# Francesco.net
KiCad netlist of a schematic drawn in EAGLE
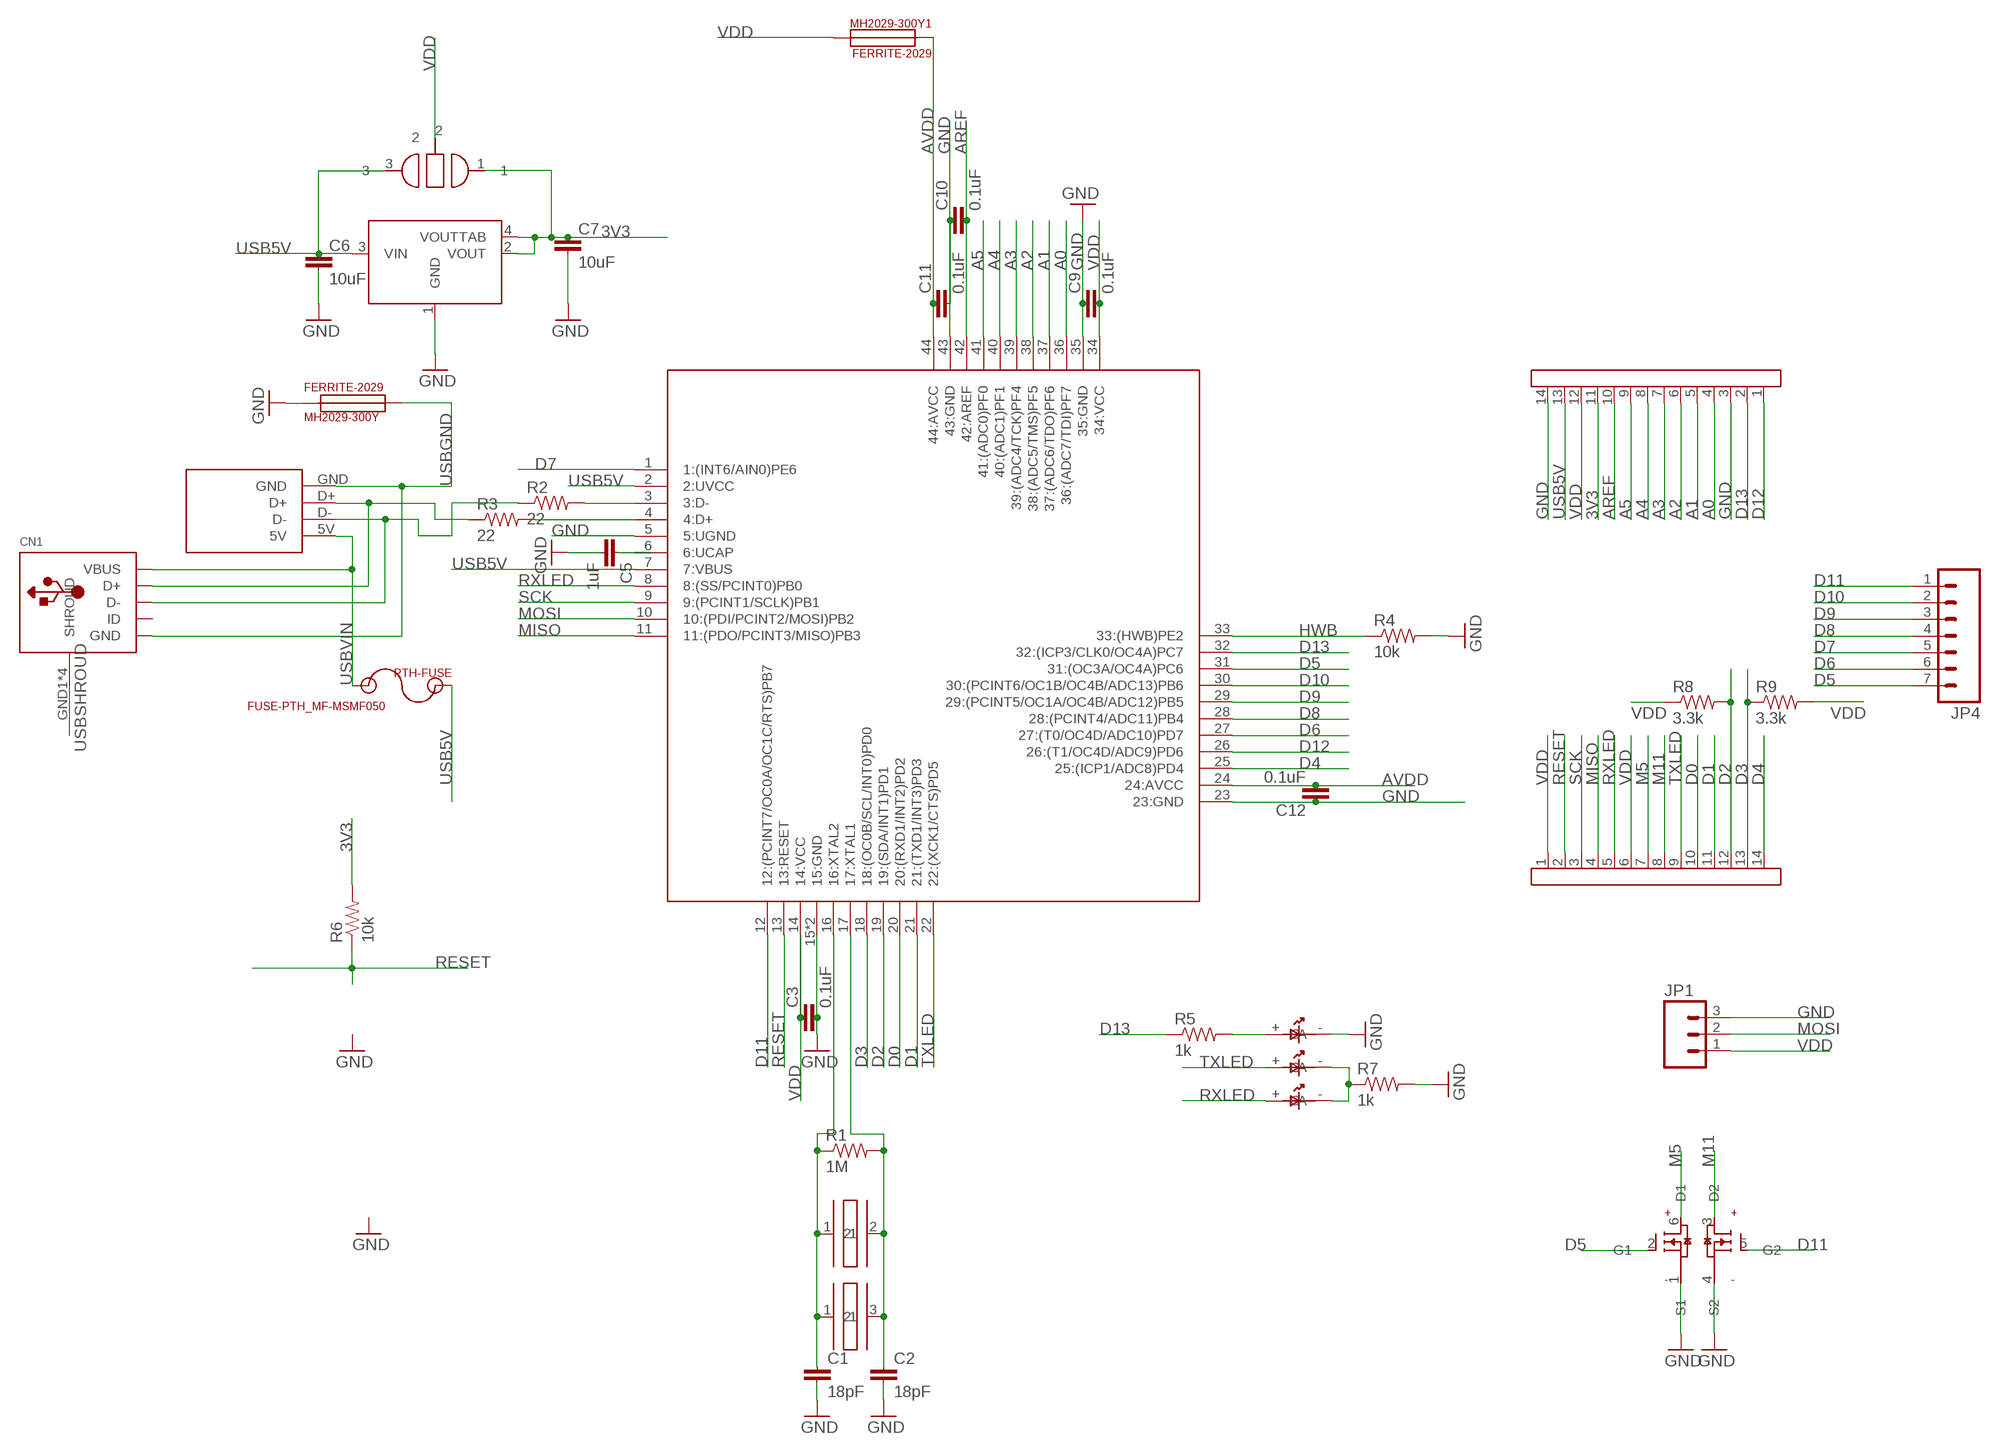
[diagram p0: schematic, sheet 1]

(export (version "E")
  (design (tool "Eeschema 10.0.6"))
  (components
    (comp (ref "C1")
      (value "18pF")
      (footprint "eagle-import:0603-CAP")
      (libsource (lib "eagle-import") (part "CAP0603-CAP"))
    )
    (comp (ref "C2")
      (value "18pF")
      (footprint "eagle-import:0603-CAP")
      (libsource (lib "eagle-import") (part "CAP0603-CAP"))
    )
    (comp (ref "C3")
      (value "0.1uF")
      (footprint "eagle-import:0805")
      (libsource (lib "eagle-import") (part "CAP0805"))
    )
    (comp (ref "C5")
      (value "1uF")
      (footprint "eagle-import:0805")
      (libsource (lib "eagle-import") (part "CAP0805"))
    )
    (comp (ref "C6")
      (value "10uF")
      (footprint "eagle-import:1210")
      (libsource (lib "eagle-import") (part "CAP1210"))
    )
    (comp (ref "C7")
      (value "10uF")
      (footprint "eagle-import:1210")
      (libsource (lib "eagle-import") (part "CAP1210"))
    )
    (comp (ref "C9")
      (value "0.1uF")
      (footprint "eagle-import:0805")
      (libsource (lib "eagle-import") (part "CAP0805"))
    )
    (comp (ref "C10")
      (value "0.1uF")
      (footprint "eagle-import:0805")
      (libsource (lib "eagle-import") (part "CAP0805"))
    )
    (comp (ref "C11")
      (value "0.1uF")
      (footprint "eagle-import:0805")
      (libsource (lib "eagle-import") (part "CAP0805"))
    )
    (comp (ref "C12")
      (value "0.1uF")
      (footprint "eagle-import:0805")
      (libsource (lib "eagle-import") (part "CAP0805"))
    )
    (comp (ref "CN1")
      (value "USBMINIB")
      (footprint "eagle-import:USB-MINIB")
      (libsource (lib "eagle-import") (part "USBMINIB"))
    )
    (comp (ref "JP1")
      (value "M03LOCK")
      (footprint "eagle-import:1X03_LOCK")
      (libsource (lib "eagle-import") (part "M03LOCK"))
    )
    (comp (ref "JP4")
      (value "M07LOCK")
      (footprint "eagle-import:1X07_LOCK")
      (libsource (lib "eagle-import") (part "M07LOCK"))
    )
    (comp (ref "MH2029-300Y")
      (value "FERRITE-2029")
      (footprint "eagle-import:2029")
      (libsource (lib "eagle-import") (part "FERRITE-2029"))
    )
    (comp (ref "MH2029-300Y1")
      (value "FERRITE-2029")
      (footprint "eagle-import:2029")
      (libsource (lib "eagle-import") (part "FERRITE-2029"))
    )
    (comp (ref "PTH-FUSE")
      (value "FUSE-PTH_MF-MSMF050")
      (footprint "eagle-import:MF-MSMF")
      (libsource (lib "eagle-import") (part "FUSE-PTH_MF-MSMF"))
    )
    (comp (ref "R1")
      (value "1M")
      (footprint "eagle-import:0805")
      (libsource (lib "eagle-import") (part "RESISTOR"))
    )
    (comp (ref "R2")
      (value "22")
      (footprint "eagle-import:0603-RES")
      (libsource (lib "eagle-import") (part "RESISTOR0603-RES"))
    )
    (comp (ref "R3")
      (value "22")
      (footprint "eagle-import:0603-RES")
      (libsource (lib "eagle-import") (part "RESISTOR0603-RES"))
    )
    (comp (ref "R4")
      (value "10k")
      (footprint "eagle-import:0805")
      (libsource (lib "eagle-import") (part "RESISTOR"))
    )
    (comp (ref "R5")
      (value "1k")
      (footprint "eagle-import:0805")
      (libsource (lib "eagle-import") (part "RESISTOR"))
    )
    (comp (ref "R6")
      (value "10k")
      (footprint "eagle-import:0805")
      (libsource (lib "eagle-import") (part "RESISTOR"))
    )
    (comp (ref "R7")
      (value "1k")
      (footprint "eagle-import:0805")
      (libsource (lib "eagle-import") (part "RESISTOR"))
    )
    (comp (ref "R8")
      (value "3.3k")
      (footprint "eagle-import:0805")
      (libsource (lib "eagle-import") (part "RESISTOR"))
    )
    (comp (ref "R9")
      (value "3.3k")
      (footprint "eagle-import:0805")
      (libsource (lib "eagle-import") (part "RESISTOR"))
    )
    (comp (ref "U$1")
      (value "ATMEGA32U4")
      (footprint "eagle-import:QFN-44")
      (libsource (lib "eagle-import") (part "ATMEGA32U4"))
    )
    (comp (ref "U$2")
      (value "HC49US")
      (footprint "eagle-import:HC49US")
      (libsource (lib "eagle-import") (part "HC49US"))
    )
    (comp (ref "U$3")
      (value "USB-PCB")
      (footprint "eagle-import:USB_PCB")
      (libsource (lib "eagle-import") (part "USB-PCB"))
    )
    (comp (ref "U$4")
      (value "5V-LDO-ZLDO1117")
      (footprint "eagle-import:ZLDO1117")
      (libsource (lib "eagle-import") (part "5V-LDO-ZLDO1117"))
    )
    (comp (ref "U$5")
      (value "M14")
      (footprint "eagle-import:1X14_LOCK")
      (libsource (lib "eagle-import") (part "M14"))
    )
    (comp (ref "U$6")
      (value "M14")
      (footprint "eagle-import:1X14_LOCK")
      (libsource (lib "eagle-import") (part "M14"))
    )
    (comp (ref "U$7")
      (value "BRIDGE-3")
      (footprint "eagle-import:BRIDGE-3")
      (libsource (lib "eagle-import") (part "BRIDGE-3"))
    )
    (comp (ref "U$8")
      (value "CRYSTAL-3.2X2.5")
      (footprint "eagle-import:XTAL3.2X2.5")
      (libsource (lib "eagle-import") (part "CRYSTAL-3.2X2.5"))
    )
    (comp (ref "U$9")
      (value "LED0805")
      (footprint "eagle-import:0805-LED")
      (libsource (lib "eagle-import") (part "LED0805"))
    )
    (comp (ref "U$10")
      (value "LED0805")
      (footprint "eagle-import:0805-LED")
      (libsource (lib "eagle-import") (part "LED0805"))
    )
    (comp (ref "U$11")
      (value "LED0805")
      (footprint "eagle-import:0805-LED")
      (libsource (lib "eagle-import") (part "LED0805"))
    )
    (comp (ref "U$12")
      (value "N-DUAL-MOSFET")
      (footprint "eagle-import:SOT-363")
      (libsource (lib "eagle-import") (part "N-DUAL-MOSFET"))
    )
  )
  (nets
    (net (code "1") (name "/3V3") (class "Default")
      (node (ref "C7") (pin "1") (pinfunction "1_1") (pintype "passive"))
      (node (ref "R6") (pin "2") (pinfunction "2_2") (pintype "passive"))
      (node (ref "U$4") (pin "2") (pinfunction "VOUT_2") (pintype "bidirectional"))
      (node (ref "U$4") (pin "4") (pinfunction "VOUTTAB_4") (pintype "bidirectional"))
      (node (ref "U$6") (pin "11") (pinfunction "11_11") (pintype "bidirectional"))
      (node (ref "U$7") (pin "1") (pinfunction "1_1") (pintype "bidirectional"))
    )
    (net (code "2") (name "/A0") (class "Default")
      (node (ref "U$1") (pin "36") (pinfunction "36:(ADC7/TDI)PF7_36") (pintype "bidirectional"))
      (node (ref "U$6") (pin "4") (pinfunction "4_4") (pintype "bidirectional"))
    )
    (net (code "3") (name "/A1") (class "Default")
      (node (ref "U$1") (pin "37") (pinfunction "37:(ADC6/TDO)PF6_37") (pintype "bidirectional"))
      (node (ref "U$6") (pin "5") (pinfunction "5_5") (pintype "bidirectional"))
    )
    (net (code "4") (name "/A2") (class "Default")
      (node (ref "U$1") (pin "38") (pinfunction "38:(ADC5/TMS)PF5_38") (pintype "bidirectional"))
      (node (ref "U$6") (pin "6") (pinfunction "6_6") (pintype "bidirectional"))
    )
    (net (code "5") (name "/A3") (class "Default")
      (node (ref "U$1") (pin "39") (pinfunction "39:(ADC4/TCK)PF4_39") (pintype "bidirectional"))
      (node (ref "U$6") (pin "7") (pinfunction "7_7") (pintype "bidirectional"))
    )
    (net (code "6") (name "/A4") (class "Default")
      (node (ref "U$1") (pin "40") (pinfunction "40:(ADC1)PF1_40") (pintype "bidirectional"))
      (node (ref "U$6") (pin "8") (pinfunction "8_8") (pintype "bidirectional"))
    )
    (net (code "7") (name "/A5") (class "Default")
      (node (ref "U$1") (pin "41") (pinfunction "41:(ADC0)PF0_41") (pintype "bidirectional"))
      (node (ref "U$6") (pin "9") (pinfunction "9_9") (pintype "bidirectional"))
    )
    (net (code "8") (name "/AREF") (class "Default")
      (node (ref "C10") (pin "2") (pinfunction "2_2") (pintype "passive"))
      (node (ref "U$1") (pin "42") (pinfunction "42:AREF_42") (pintype "bidirectional"))
      (node (ref "U$6") (pin "10") (pinfunction "10_10") (pintype "bidirectional"))
    )
    (net (code "9") (name "/AVDD") (class "Default")
      (node (ref "C11") (pin "1") (pinfunction "1_1") (pintype "passive"))
      (node (ref "C12") (pin "2") (pinfunction "2_2") (pintype "passive"))
      (node (ref "MH2029-300Y1") (pin "P$1") (pinfunction "P$1_P$1") (pintype "bidirectional"))
      (node (ref "U$1") (pin "24") (pinfunction "24:AVCC_24") (pintype "bidirectional"))
      (node (ref "U$1") (pin "44") (pinfunction "44:AVCC_44") (pintype "bidirectional"))
    )
    (net (code "10") (name "/D0") (class "Default")
      (node (ref "U$1") (pin "20") (pinfunction "20:(RXD1/INT2)PD2_20") (pintype "bidirectional"))
      (node (ref "U$5") (pin "10") (pinfunction "10_10") (pintype "bidirectional"))
    )
    (net (code "11") (name "/D1") (class "Default")
      (node (ref "U$1") (pin "21") (pinfunction "21:(TXD1/INT3)PD3_21") (pintype "bidirectional"))
      (node (ref "U$5") (pin "11") (pinfunction "11_11") (pintype "bidirectional"))
    )
    (net (code "12") (name "/D2") (class "Default")
      (node (ref "R8") (pin "2") (pinfunction "2_2") (pintype "passive"))
      (node (ref "U$1") (pin "19") (pinfunction "19:(SDA/INT1)PD1_19") (pintype "bidirectional"))
      (node (ref "U$5") (pin "12") (pinfunction "12_12") (pintype "bidirectional"))
    )
    (net (code "13") (name "/D3") (class "Default")
      (node (ref "R9") (pin "1") (pinfunction "1_1") (pintype "passive"))
      (node (ref "U$1") (pin "18") (pinfunction "18:(OC0B/SCL/INT0)PD0_18") (pintype "bidirectional"))
      (node (ref "U$5") (pin "13") (pinfunction "13_13") (pintype "bidirectional"))
    )
    (net (code "14") (name "/D4") (class "Default")
      (node (ref "U$1") (pin "25") (pinfunction "25:(ICP1/ADC8)PD4_25") (pintype "bidirectional"))
      (node (ref "U$5") (pin "14") (pinfunction "14_14") (pintype "bidirectional"))
    )
    (net (code "15") (name "/D5") (class "Default")
      (node (ref "JP4") (pin "7") (pinfunction "7_7") (pintype "passive"))
      (node (ref "U$1") (pin "31") (pinfunction "31:(OC3A/OC4A)PC6_31") (pintype "bidirectional"))
      (node (ref "U$12") (pin "2") (pinfunction "G1_2") (pintype "bidirectional"))
    )
    (net (code "16") (name "/D6") (class "Default")
      (node (ref "JP4") (pin "6") (pinfunction "6_6") (pintype "passive"))
      (node (ref "U$1") (pin "27") (pinfunction "27:(T0/OC4D/ADC10)PD7_27") (pintype "bidirectional"))
    )
    (net (code "17") (name "/D7") (class "Default")
      (node (ref "JP4") (pin "5") (pinfunction "5_5") (pintype "passive"))
      (node (ref "U$1") (pin "1") (pinfunction "1:(INT6/AIN0)PE6_1") (pintype "bidirectional"))
    )
    (net (code "18") (name "/D8") (class "Default")
      (node (ref "JP4") (pin "4") (pinfunction "4_4") (pintype "passive"))
      (node (ref "U$1") (pin "28") (pinfunction "28:(PCINT4/ADC11)PB4_28") (pintype "bidirectional"))
    )
    (net (code "19") (name "/D9") (class "Default")
      (node (ref "JP4") (pin "3") (pinfunction "3_3") (pintype "passive"))
      (node (ref "U$1") (pin "29") (pinfunction "29:(PCINT5/OC1A/OC4B/ADC12)PB5_29") (pintype "bidirectional"))
    )
    (net (code "20") (name "/D10") (class "Default")
      (node (ref "JP4") (pin "2") (pinfunction "2_2") (pintype "passive"))
      (node (ref "U$1") (pin "30") (pinfunction "30:(PCINT6/OC1B/OC4B/ADC13)PB6_30") (pintype "bidirectional"))
    )
    (net (code "21") (name "/D11") (class "Default")
      (node (ref "JP4") (pin "1") (pinfunction "1_1") (pintype "passive"))
      (node (ref "U$1") (pin "12") (pinfunction "12:(PCINT7/OC0A/OC1C/RTS)PB7_12") (pintype "bidirectional"))
      (node (ref "U$12") (pin "5") (pinfunction "G2_5") (pintype "bidirectional"))
    )
    (net (code "22") (name "/D12") (class "Default")
      (node (ref "U$1") (pin "26") (pinfunction "26:(T1/OC4D/ADC9)PD6_26") (pintype "bidirectional"))
      (node (ref "U$6") (pin "1") (pinfunction "1_1") (pintype "bidirectional"))
    )
    (net (code "23") (name "/D13") (class "Default")
      (node (ref "R5") (pin "1") (pinfunction "1_1") (pintype "passive"))
      (node (ref "U$1") (pin "32") (pinfunction "32:(ICP3/CLK0/OC4A)PC7_32") (pintype "bidirectional"))
      (node (ref "U$6") (pin "2") (pinfunction "2_2") (pintype "bidirectional"))
    )
    (net (code "24") (name "/HWB") (class "Default")
      (node (ref "R4") (pin "1") (pinfunction "1_1") (pintype "passive"))
      (node (ref "U$1") (pin "33") (pinfunction "33:(HWB)PE2_33") (pintype "bidirectional"))
    )
    (net (code "25") (name "/M5") (class "Default")
      (node (ref "U$12") (pin "6") (pinfunction "D1_6") (pintype "bidirectional"))
      (node (ref "U$5") (pin "7") (pinfunction "7_7") (pintype "bidirectional"))
    )
    (net (code "26") (name "/M11") (class "Default")
      (node (ref "U$12") (pin "3") (pinfunction "D2_3") (pintype "bidirectional"))
      (node (ref "U$5") (pin "8") (pinfunction "8_8") (pintype "bidirectional"))
    )
    (net (code "27") (name "/MISO") (class "Default")
      (node (ref "U$1") (pin "11") (pinfunction "11:(PDO/PCINT3/MISO)PB3_11") (pintype "bidirectional"))
      (node (ref "U$5") (pin "4") (pinfunction "4_4") (pintype "bidirectional"))
    )
    (net (code "28") (name "/MOSI") (class "Default")
      (node (ref "JP1") (pin "2") (pinfunction "2_2") (pintype "passive"))
      (node (ref "U$1") (pin "10") (pinfunction "10:(PDI/PCINT2/MOSI)PB2_10") (pintype "bidirectional"))
    )
    (net (code "29") (name "/RESET") (class "Default")
      (node (ref "R6") (pin "1") (pinfunction "1_1") (pintype "passive"))
      (node (ref "U$1") (pin "13") (pinfunction "13:RESET_13") (pintype "bidirectional"))
      (node (ref "U$5") (pin "2") (pinfunction "2_2") (pintype "bidirectional"))
    )
    (net (code "30") (name "/RXLED") (class "Default")
      (node (ref "U$1") (pin "8") (pinfunction "8:(SS/PCINT0)PB0_8") (pintype "bidirectional"))
      (node (ref "U$11") (pin "+") (pinfunction "A_+") (pintype "bidirectional"))
      (node (ref "U$5") (pin "5") (pinfunction "5_5") (pintype "bidirectional"))
    )
    (net (code "31") (name "/SCK") (class "Default")
      (node (ref "U$1") (pin "9") (pinfunction "9:(PCINT1/SCLK)PB1_9") (pintype "bidirectional"))
      (node (ref "U$5") (pin "3") (pinfunction "3_3") (pintype "bidirectional"))
    )
    (net (code "32") (name "/TXLED") (class "Default")
      (node (ref "U$1") (pin "22") (pinfunction "22:(XCK1/CTS)PD5_22") (pintype "bidirectional"))
      (node (ref "U$10") (pin "+") (pinfunction "A_+") (pintype "bidirectional"))
      (node (ref "U$5") (pin "9") (pinfunction "9_9") (pintype "bidirectional"))
    )
    (net (code "33") (name "/USB5V") (class "Default")
      (node (ref "C6") (pin "1") (pinfunction "1_1") (pintype "passive"))
      (node (ref "PTH-FUSE") (pin "P$1") (pinfunction "P$1_P$1") (pintype "bidirectional"))
      (node (ref "U$1") (pin "2") (pinfunction "2:UVCC_2") (pintype "bidirectional"))
      (node (ref "U$1") (pin "7") (pinfunction "7:VBUS_7") (pintype "bidirectional"))
      (node (ref "U$4") (pin "3") (pinfunction "VIN_3") (pintype "bidirectional"))
      (node (ref "U$6") (pin "13") (pinfunction "13_13") (pintype "bidirectional"))
      (node (ref "U$7") (pin "3") (pinfunction "3_3") (pintype "bidirectional"))
    )
    (net (code "34") (name "/USBGND") (class "Default")
      (node (ref "CN1") (pin "GND") (pinfunction "GND_GND") (pintype "power_in"))
      (node (ref "MH2029-300Y") (pin "P$2") (pinfunction "P$2_P$2") (pintype "bidirectional"))
      (node (ref "U$3") (pin "GND") (pinfunction "GND_GND") (pintype "bidirectional"))
    )
    (net (code "35") (name "/USBSHROUD") (class "Default")
      (node (ref "CN1") (pin "GND1") (pinfunction "SHROUD_GND1") (pintype "bidirectional"))
      (node (ref "CN1") (pin "GND2") (pinfunction "SHROUD_GND2") (pintype "bidirectional"))
      (node (ref "CN1") (pin "GND3") (pinfunction "SHROUD_GND3") (pintype "bidirectional"))
      (node (ref "CN1") (pin "GND4") (pinfunction "SHROUD_GND4") (pintype "bidirectional"))
    )
    (net (code "36") (name "/USBVIN") (class "Default")
      (node (ref "CN1") (pin "VBUS") (pinfunction "VBUS_VBUS") (pintype "power_in"))
      (node (ref "PTH-FUSE") (pin "P$2") (pinfunction "P$2_P$2") (pintype "bidirectional"))
      (node (ref "U$3") (pin "5V") (pinfunction "5V_5V") (pintype "bidirectional"))
    )
    (net (code "37") (name "/VDD") (class "Default")
      (node (ref "C3") (pin "1") (pinfunction "1_1") (pintype "passive"))
      (node (ref "C9") (pin "2") (pinfunction "2_2") (pintype "passive"))
      (node (ref "JP1") (pin "1") (pinfunction "1_1") (pintype "passive"))
      (node (ref "MH2029-300Y1") (pin "P$2") (pinfunction "P$2_P$2") (pintype "bidirectional"))
      (node (ref "R8") (pin "1") (pinfunction "1_1") (pintype "passive"))
      (node (ref "R9") (pin "2") (pinfunction "2_2") (pintype "passive"))
      (node (ref "U$1") (pin "14") (pinfunction "14:VCC_14") (pintype "bidirectional"))
      (node (ref "U$1") (pin "34") (pinfunction "34:VCC_34") (pintype "bidirectional"))
      (node (ref "U$5") (pin "1") (pinfunction "1_1") (pintype "bidirectional"))
      (node (ref "U$5") (pin "6") (pinfunction "6_6") (pintype "bidirectional"))
      (node (ref "U$6") (pin "12") (pinfunction "12_12") (pintype "bidirectional"))
      (node (ref "U$7") (pin "2") (pinfunction "2_2") (pintype "bidirectional"))
    )
    (net (code "38") (name "GND") (class "Default")
      (node (ref "C1") (pin "2") (pinfunction "2_2") (pintype "passive"))
      (node (ref "C10") (pin "1") (pinfunction "1_1") (pintype "passive"))
      (node (ref "C11") (pin "2") (pinfunction "2_2") (pintype "passive"))
      (node (ref "C12") (pin "1") (pinfunction "1_1") (pintype "passive"))
      (node (ref "C2") (pin "2") (pinfunction "2_2") (pintype "passive"))
      (node (ref "C3") (pin "2") (pinfunction "2_2") (pintype "passive"))
      (node (ref "C5") (pin "2") (pinfunction "2_2") (pintype "passive"))
      (node (ref "C6") (pin "2") (pinfunction "2_2") (pintype "passive"))
      (node (ref "C7") (pin "2") (pinfunction "2_2") (pintype "passive"))
      (node (ref "C9") (pin "1") (pinfunction "1_1") (pintype "passive"))
      (node (ref "JP1") (pin "3") (pinfunction "3_3") (pintype "passive"))
      (node (ref "MH2029-300Y") (pin "P$1") (pinfunction "P$1_P$1") (pintype "bidirectional"))
      (node (ref "R4") (pin "2") (pinfunction "2_2") (pintype "passive"))
      (node (ref "R7") (pin "2") (pinfunction "2_2") (pintype "passive"))
      (node (ref "U$1") (pin "15") (pinfunction "15:GND_15") (pintype "bidirectional"))
      (node (ref "U$1") (pin "23") (pinfunction "23:GND_23") (pintype "bidirectional"))
      (node (ref "U$1") (pin "35") (pinfunction "35:GND_35") (pintype "bidirectional"))
      (node (ref "U$1") (pin "43") (pinfunction "43:GND_43") (pintype "bidirectional"))
      (node (ref "U$1") (pin "5") (pinfunction "5:UGND_5") (pintype "bidirectional"))
      (node (ref "U$1") (pin "PAD") (pinfunction "15:GND_PAD") (pintype "bidirectional"))
      (node (ref "U$12") (pin "1") (pinfunction "S1_1") (pintype "bidirectional"))
      (node (ref "U$12") (pin "4") (pinfunction "S2_4") (pintype "bidirectional"))
      (node (ref "U$4") (pin "1") (pinfunction "GND_1") (pintype "bidirectional"))
      (node (ref "U$6") (pin "14") (pinfunction "14_14") (pintype "bidirectional"))
      (node (ref "U$6") (pin "3") (pinfunction "3_3") (pintype "bidirectional"))
      (node (ref "U$9") (pin "-") (pinfunction "C_-") (pintype "bidirectional"))
    )
    (net (code "39") (name "Net-(CN1-PadD+)") (class "Default")
      (node (ref "CN1") (pin "D+") (pinfunction "D+_D+") (pintype "bidirectional"))
      (node (ref "R3") (pin "1") (pinfunction "1_1") (pintype "passive"))
      (node (ref "U$3") (pin "D+") (pinfunction "D+_D+") (pintype "bidirectional"))
    )
    (net (code "40") (name "Net-(CN1-PadD-)") (class "Default")
      (node (ref "CN1") (pin "D-") (pinfunction "D-_D-") (pintype "bidirectional"))
      (node (ref "R2") (pin "1") (pinfunction "1_1") (pintype "passive"))
      (node (ref "U$3") (pin "D-") (pinfunction "D-_D-") (pintype "bidirectional"))
    )
    (net (code "41") (name "Net-(U$1-3:D-)") (class "Default")
      (node (ref "R2") (pin "2") (pinfunction "2_2") (pintype "passive"))
      (node (ref "U$1") (pin "3") (pinfunction "3:D-_3") (pintype "bidirectional"))
    )
    (net (code "42") (name "Net-(U$1-4:D+)") (class "Default")
      (node (ref "R3") (pin "2") (pinfunction "2_2") (pintype "passive"))
      (node (ref "U$1") (pin "4") (pinfunction "4:D+_4") (pintype "bidirectional"))
    )
    (net (code "43") (name "Net-(U$1-6:UCAP)") (class "Default")
      (node (ref "C5") (pin "1") (pinfunction "1_1") (pintype "passive"))
      (node (ref "U$1") (pin "6") (pinfunction "6:UCAP_6") (pintype "bidirectional"))
    )
    (net (code "44") (name "Net-(U$1-16:XTAL2)") (class "Default")
      (node (ref "C1") (pin "1") (pinfunction "1_1") (pintype "passive"))
      (node (ref "R1") (pin "1") (pinfunction "1_1") (pintype "passive"))
      (node (ref "U$1") (pin "16") (pinfunction "16:XTAL2_16") (pintype "bidirectional"))
      (node (ref "U$2") (pin "1") (pinfunction "1_1") (pintype "bidirectional"))
      (node (ref "U$8") (pin "1") (pinfunction "1_1") (pintype "bidirectional"))
    )
    (net (code "45") (name "Net-(U$1-17:XTAL1)") (class "Default")
      (node (ref "C2") (pin "1") (pinfunction "1_1") (pintype "passive"))
      (node (ref "R1") (pin "2") (pinfunction "2_2") (pintype "passive"))
      (node (ref "U$1") (pin "17") (pinfunction "17:XTAL1_17") (pintype "bidirectional"))
      (node (ref "U$2") (pin "2") (pinfunction "2_2") (pintype "bidirectional"))
      (node (ref "U$8") (pin "3") (pinfunction "2_3") (pintype "bidirectional"))
    )
    (net (code "46") (name "Net-(U$9-A)") (class "Default")
      (node (ref "R5") (pin "2") (pinfunction "2_2") (pintype "passive"))
      (node (ref "U$9") (pin "+") (pinfunction "A_+") (pintype "bidirectional"))
    )
    (net (code "47") (name "Net-(U$10-C)") (class "Default")
      (node (ref "R7") (pin "1") (pinfunction "1_1") (pintype "passive"))
      (node (ref "U$10") (pin "-") (pinfunction "C_-") (pintype "bidirectional"))
      (node (ref "U$11") (pin "-") (pinfunction "C_-") (pintype "bidirectional"))
    )
    (net (code "48") (name "unconnected-(CN1-PadID)") (class "Default")
      (node (ref "CN1") (pin "ID") (pinfunction "ID_ID") (pintype "bidirectional"))
    )
  )
)
